# GTM_BallGrippersCircuits.net
KiCad netlist of a schematic drawn in Altium Designer
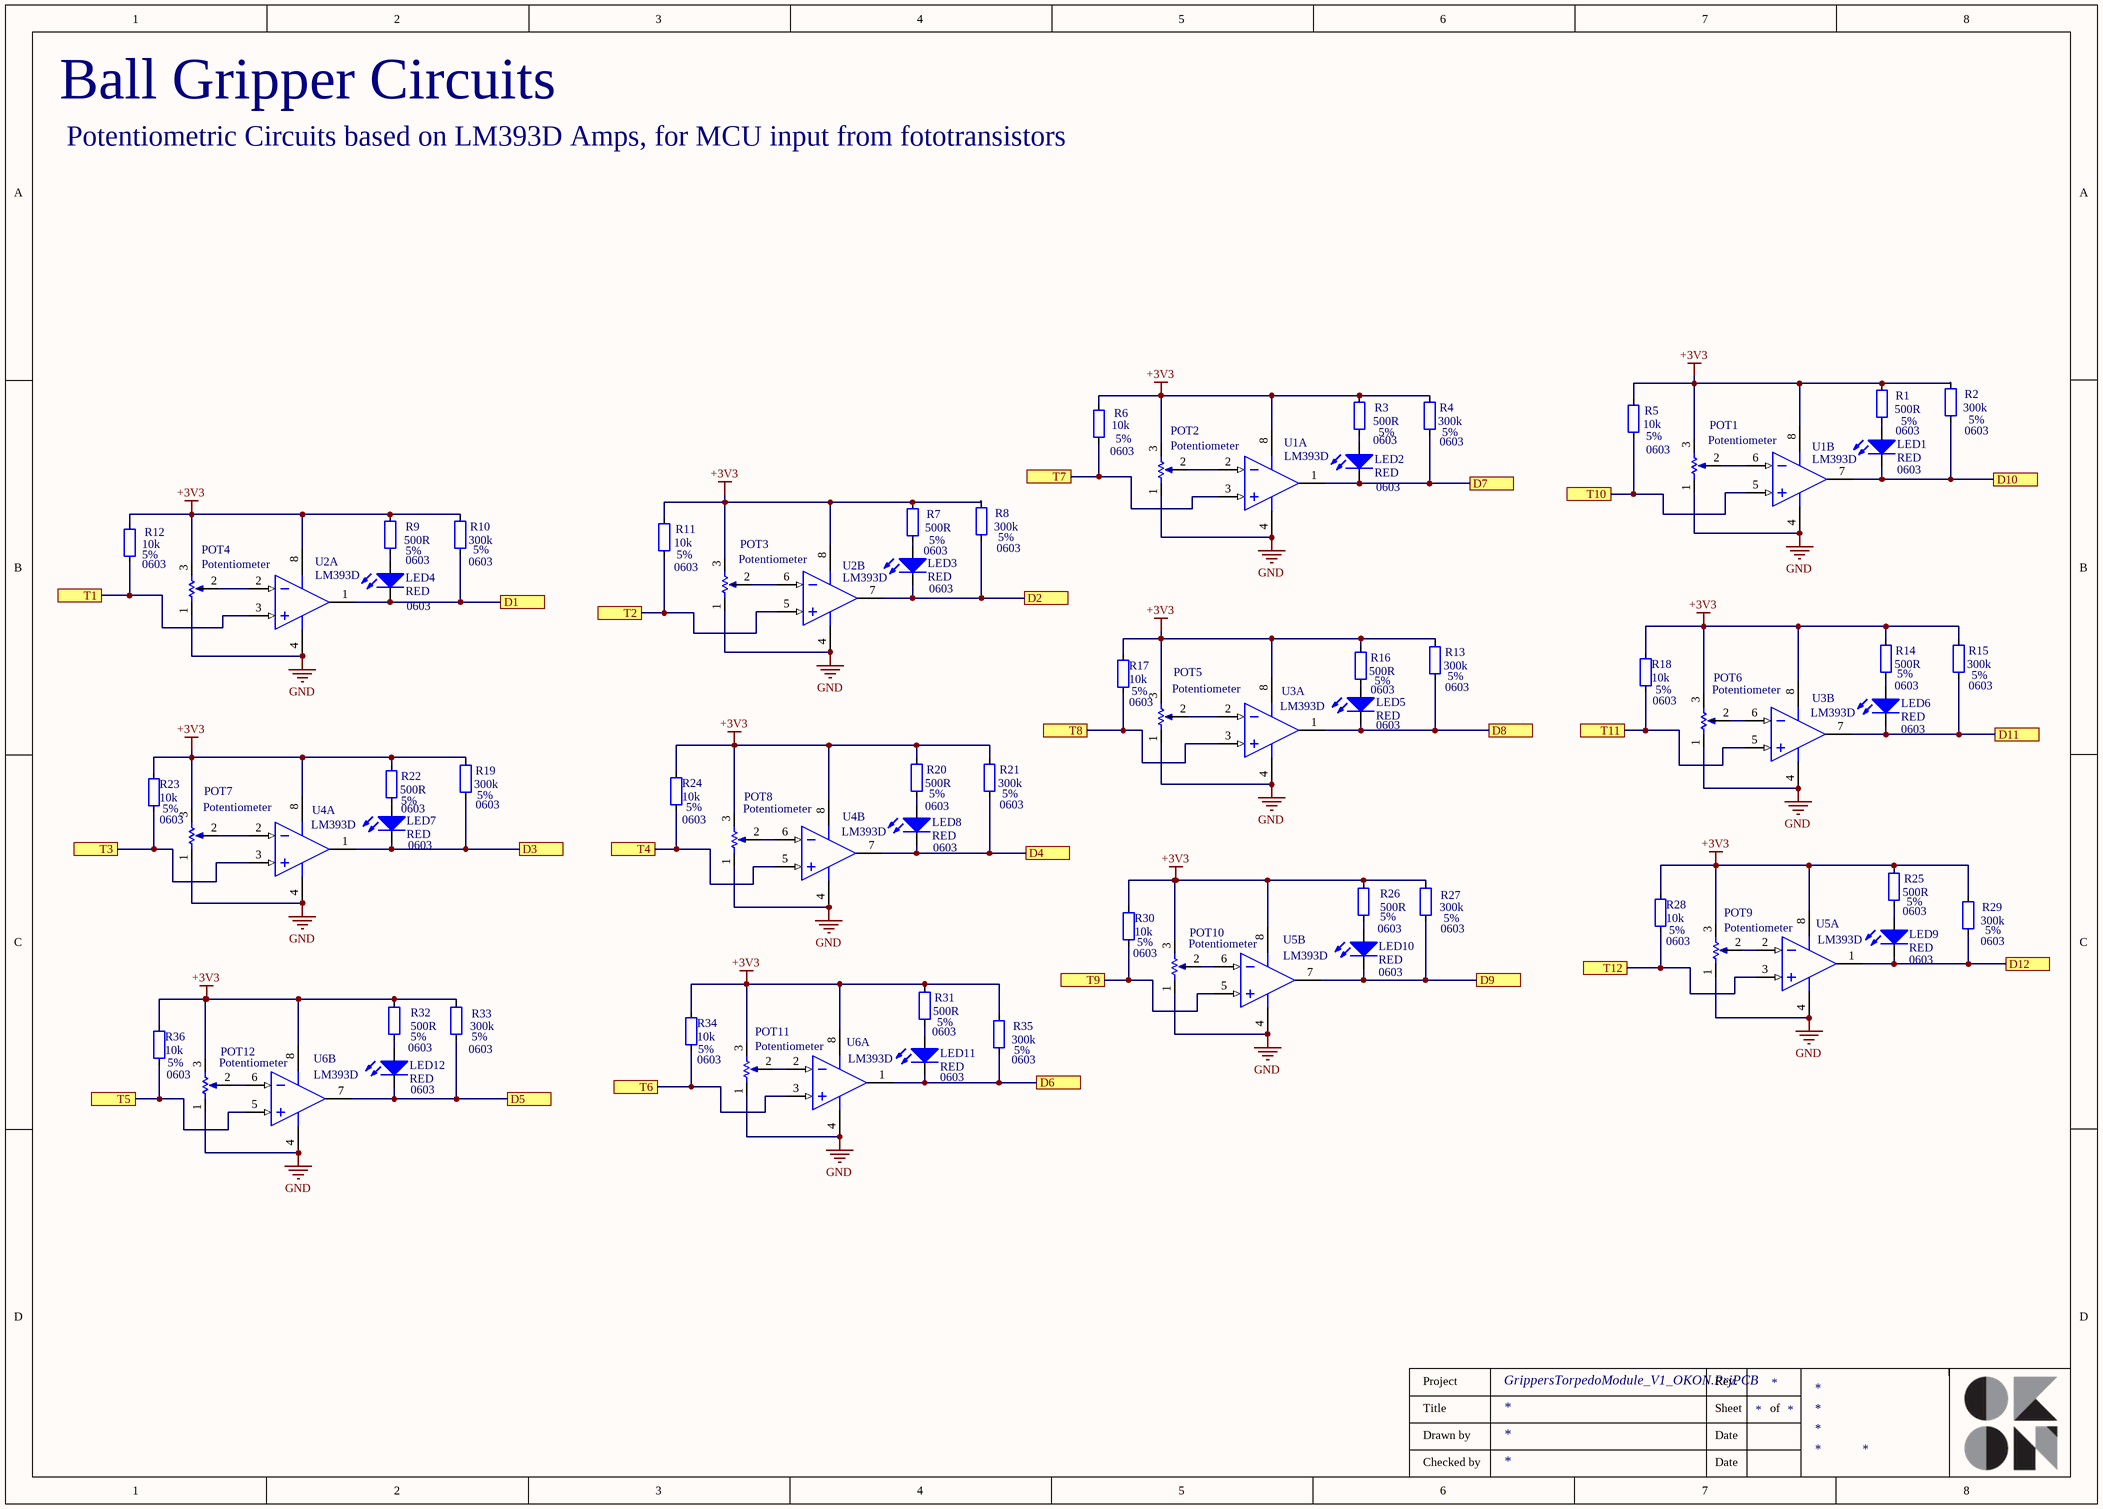
[diagram p0: GTM_BallGrippersCircuits.SchDoc]

(export (version "E")
  (design (tool "Eeschema 10.0.6"))
  (components
    (comp (ref "LED1")
      (value "RED")
      (footprint "0603_led_red")
      (description "Light-emitting diode")
      (fields (field (name "PACKAGE") "0603"))
      (libsource (lib "KNR_Kurs") (part "LED"))
    )
    (comp (ref "LED2")
      (value "RED")
      (footprint "0603_led_red")
      (description "Light-emitting diode")
      (fields (field (name "PACKAGE") "0603"))
      (libsource (lib "KNR_Kurs") (part "LED"))
    )
    (comp (ref "LED3")
      (value "RED")
      (footprint "0603_led_red")
      (description "Light-emitting diode")
      (fields (field (name "PACKAGE") "0603"))
      (libsource (lib "KNR_Kurs") (part "LED"))
    )
    (comp (ref "LED4")
      (value "RED")
      (footprint "0603_led_red")
      (description "Light-emitting diode")
      (fields (field (name "PACKAGE") "0603"))
      (libsource (lib "KNR_Kurs") (part "LED"))
    )
    (comp (ref "LED5")
      (value "RED")
      (footprint "0603_led_red")
      (description "Light-emitting diode")
      (fields (field (name "PACKAGE") "0603"))
      (libsource (lib "KNR_Kurs") (part "LED"))
    )
    (comp (ref "LED6")
      (value "RED")
      (footprint "0603_led_red")
      (description "Light-emitting diode")
      (fields (field (name "PACKAGE") "0603"))
      (libsource (lib "KNR_Kurs") (part "LED"))
    )
    (comp (ref "LED7")
      (value "RED")
      (footprint "0603_led_red")
      (description "Light-emitting diode")
      (fields (field (name "PACKAGE") "0603"))
      (libsource (lib "KNR_Kurs") (part "LED"))
    )
    (comp (ref "LED8")
      (value "RED")
      (footprint "0603_led_red")
      (description "Light-emitting diode")
      (fields (field (name "PACKAGE") "0603"))
      (libsource (lib "KNR_Kurs") (part "LED"))
    )
    (comp (ref "LED9")
      (value "RED")
      (footprint "0603_led_red")
      (description "Light-emitting diode")
      (fields (field (name "PACKAGE") "0603"))
      (libsource (lib "KNR_Kurs") (part "LED"))
    )
    (comp (ref "LED10")
      (value "RED")
      (footprint "0603_led_red")
      (description "Light-emitting diode")
      (fields (field (name "PACKAGE") "0603"))
      (libsource (lib "KNR_Kurs") (part "LED"))
    )
    (comp (ref "LED11")
      (value "RED")
      (footprint "0603_led_red")
      (description "Light-emitting diode")
      (fields (field (name "PACKAGE") "0603"))
      (libsource (lib "KNR_Kurs") (part "LED"))
    )
    (comp (ref "LED12")
      (value "RED")
      (footprint "0603_led_red")
      (description "Light-emitting diode")
      (fields (field (name "PACKAGE") "0603"))
      (libsource (lib "KNR_Kurs") (part "LED"))
    )
    (comp (ref "POT1")
      (value "Potentiometer")
      (footprint "Pot_3296")
      (libsource (lib "Library_Altium_KNR") (part "Potentiometer"))
    )
    (comp (ref "POT2")
      (value "Potentiometer")
      (footprint "Pot_3296")
      (libsource (lib "Library_Altium_KNR") (part "Potentiometer"))
    )
    (comp (ref "POT3")
      (value "Potentiometer")
      (footprint "Pot_3296")
      (libsource (lib "Library_Altium_KNR") (part "Potentiometer"))
    )
    (comp (ref "POT4")
      (value "Potentiometer")
      (footprint "Pot_3296")
      (libsource (lib "Library_Altium_KNR") (part "Potentiometer"))
    )
    (comp (ref "POT5")
      (value "Potentiometer")
      (footprint "Pot_3296")
      (libsource (lib "Library_Altium_KNR") (part "Potentiometer"))
    )
    (comp (ref "POT6")
      (value "Potentiometer")
      (footprint "Pot_3296")
      (libsource (lib "Library_Altium_KNR") (part "Potentiometer"))
    )
    (comp (ref "POT7")
      (value "Potentiometer")
      (footprint "Pot_3296")
      (libsource (lib "Library_Altium_KNR") (part "Potentiometer"))
    )
    (comp (ref "POT8")
      (value "Potentiometer")
      (footprint "Pot_3296")
      (libsource (lib "Library_Altium_KNR") (part "Potentiometer"))
    )
    (comp (ref "POT9")
      (value "Potentiometer")
      (footprint "Pot_3296")
      (libsource (lib "Library_Altium_KNR") (part "Potentiometer"))
    )
    (comp (ref "POT10")
      (value "Potentiometer")
      (footprint "Pot_3296")
      (libsource (lib "Library_Altium_KNR") (part "Potentiometer"))
    )
    (comp (ref "POT11")
      (value "Potentiometer")
      (footprint "Pot_3296")
      (libsource (lib "Library_Altium_KNR") (part "Potentiometer"))
    )
    (comp (ref "POT12")
      (value "Potentiometer")
      (footprint "Pot_3296")
      (libsource (lib "Library_Altium_KNR") (part "Potentiometer"))
    )
    (comp (ref "R1")
      (value "500R")
      (footprint "0603")
      (description "Resistior")
      (fields (field (name "PACKAGE") "0603") (field (name "TOLERANCE") "5%"))
      (libsource (lib "Library_Altium_KNR") (part "RES"))
    )
    (comp (ref "R2")
      (value "300k")
      (footprint "0603")
      (description "Resistior")
      (fields (field (name "PACKAGE") "0603") (field (name "TOLERANCE") "5%"))
      (libsource (lib "Library_Altium_KNR") (part "RES"))
    )
    (comp (ref "R3")
      (value "500R")
      (footprint "0603")
      (description "Resistior")
      (fields (field (name "PACKAGE") "0603") (field (name "TOLERANCE") "5%"))
      (libsource (lib "Library_Altium_KNR") (part "RES"))
    )
    (comp (ref "R4")
      (value "300k")
      (footprint "0603")
      (description "Resistior")
      (fields (field (name "PACKAGE") "0603") (field (name "TOLERANCE") "5%"))
      (libsource (lib "Library_Altium_KNR") (part "RES"))
    )
    (comp (ref "R5")
      (value "10k")
      (footprint "0603")
      (description "Resistior")
      (fields (field (name "PACKAGE") "0603") (field (name "TOLERANCE") "5%"))
      (libsource (lib "Library_Altium_KNR") (part "RES"))
    )
    (comp (ref "R6")
      (value "10k")
      (footprint "0603")
      (description "Resistior")
      (fields (field (name "PACKAGE") "0603") (field (name "TOLERANCE") "5%"))
      (libsource (lib "Library_Altium_KNR") (part "RES"))
    )
    (comp (ref "R7")
      (value "500R")
      (footprint "0603")
      (description "Resistior")
      (fields (field (name "PACKAGE") "0603") (field (name "TOLERANCE") "5%"))
      (libsource (lib "Library_Altium_KNR") (part "RES"))
    )
    (comp (ref "R8")
      (value "300k")
      (footprint "0603")
      (description "Resistior")
      (fields (field (name "PACKAGE") "0603") (field (name "TOLERANCE") "5%"))
      (libsource (lib "Library_Altium_KNR") (part "RES"))
    )
    (comp (ref "R9")
      (value "500R")
      (footprint "0603")
      (description "Resistior")
      (fields (field (name "PACKAGE") "0603") (field (name "TOLERANCE") "5%"))
      (libsource (lib "Library_Altium_KNR") (part "RES"))
    )
    (comp (ref "R10")
      (value "300k")
      (footprint "0603")
      (description "Resistior")
      (fields (field (name "PACKAGE") "0603") (field (name "TOLERANCE") "5%"))
      (libsource (lib "Library_Altium_KNR") (part "RES"))
    )
    (comp (ref "R11")
      (value "10k")
      (footprint "0603")
      (description "Resistior")
      (fields (field (name "PACKAGE") "0603") (field (name "TOLERANCE") "5%"))
      (libsource (lib "Library_Altium_KNR") (part "RES"))
    )
    (comp (ref "R12")
      (value "10k")
      (footprint "0603")
      (description "Resistior")
      (fields (field (name "PACKAGE") "0603") (field (name "TOLERANCE") "5%"))
      (libsource (lib "Library_Altium_KNR") (part "RES"))
    )
    (comp (ref "R13")
      (value "300k")
      (footprint "0603")
      (description "Resistior")
      (fields (field (name "PACKAGE") "0603") (field (name "TOLERANCE") "5%"))
      (libsource (lib "Library_Altium_KNR") (part "RES"))
    )
    (comp (ref "R14")
      (value "500R")
      (footprint "0603")
      (description "Resistior")
      (fields (field (name "PACKAGE") "0603") (field (name "TOLERANCE") "5%"))
      (libsource (lib "Library_Altium_KNR") (part "RES"))
    )
    (comp (ref "R15")
      (value "300k")
      (footprint "0603")
      (description "Resistior")
      (fields (field (name "PACKAGE") "0603") (field (name "TOLERANCE") "5%"))
      (libsource (lib "Library_Altium_KNR") (part "RES"))
    )
    (comp (ref "R16")
      (value "500R")
      (footprint "0603")
      (description "Resistior")
      (fields (field (name "PACKAGE") "0603") (field (name "TOLERANCE") "5%"))
      (libsource (lib "Library_Altium_KNR") (part "RES"))
    )
    (comp (ref "R17")
      (value "10k")
      (footprint "0603")
      (description "Resistior")
      (fields (field (name "PACKAGE") "0603") (field (name "TOLERANCE") "5%"))
      (libsource (lib "Library_Altium_KNR") (part "RES"))
    )
    (comp (ref "R18")
      (value "10k")
      (footprint "0603")
      (description "Resistior")
      (fields (field (name "PACKAGE") "0603") (field (name "TOLERANCE") "5%"))
      (libsource (lib "Library_Altium_KNR") (part "RES"))
    )
    (comp (ref "R19")
      (value "300k")
      (footprint "0603")
      (description "Resistior")
      (fields (field (name "PACKAGE") "0603") (field (name "TOLERANCE") "5%"))
      (libsource (lib "Library_Altium_KNR") (part "RES"))
    )
    (comp (ref "R20")
      (value "500R")
      (footprint "0603")
      (description "Resistior")
      (fields (field (name "PACKAGE") "0603") (field (name "TOLERANCE") "5%"))
      (libsource (lib "Library_Altium_KNR") (part "RES"))
    )
    (comp (ref "R21")
      (value "300k")
      (footprint "0603")
      (description "Resistior")
      (fields (field (name "PACKAGE") "0603") (field (name "TOLERANCE") "5%"))
      (libsource (lib "Library_Altium_KNR") (part "RES"))
    )
    (comp (ref "R22")
      (value "500R")
      (footprint "0603")
      (description "Resistior")
      (fields (field (name "PACKAGE") "0603") (field (name "TOLERANCE") "5%"))
      (libsource (lib "Library_Altium_KNR") (part "RES"))
    )
    (comp (ref "R23")
      (value "10k")
      (footprint "0603")
      (description "Resistior")
      (fields (field (name "PACKAGE") "0603") (field (name "TOLERANCE") "5%"))
      (libsource (lib "Library_Altium_KNR") (part "RES"))
    )
    (comp (ref "R24")
      (value "10k")
      (footprint "0603")
      (description "Resistior")
      (fields (field (name "PACKAGE") "0603") (field (name "TOLERANCE") "5%"))
      (libsource (lib "Library_Altium_KNR") (part "RES"))
    )
    (comp (ref "R25")
      (value "500R")
      (footprint "0603")
      (description "Resistior")
      (fields (field (name "PACKAGE") "0603") (field (name "TOLERANCE") "5%"))
      (libsource (lib "Library_Altium_KNR") (part "RES"))
    )
    (comp (ref "R26")
      (value "500R")
      (footprint "0603")
      (description "Resistior")
      (fields (field (name "PACKAGE") "0603") (field (name "TOLERANCE") "5%"))
      (libsource (lib "Library_Altium_KNR") (part "RES"))
    )
    (comp (ref "R27")
      (value "300k")
      (footprint "0603")
      (description "Resistior")
      (fields (field (name "PACKAGE") "0603") (field (name "TOLERANCE") "5%"))
      (libsource (lib "Library_Altium_KNR") (part "RES"))
    )
    (comp (ref "R28")
      (value "10k")
      (footprint "0603")
      (description "Resistior")
      (fields (field (name "PACKAGE") "0603") (field (name "TOLERANCE") "5%"))
      (libsource (lib "Library_Altium_KNR") (part "RES"))
    )
    (comp (ref "R29")
      (value "300k")
      (footprint "0603")
      (description "Resistior")
      (fields (field (name "PACKAGE") "0603") (field (name "TOLERANCE") "5%"))
      (libsource (lib "Library_Altium_KNR") (part "RES"))
    )
    (comp (ref "R30")
      (value "10k")
      (footprint "0603")
      (description "Resistior")
      (fields (field (name "PACKAGE") "0603") (field (name "TOLERANCE") "5%"))
      (libsource (lib "Library_Altium_KNR") (part "RES"))
    )
    (comp (ref "R31")
      (value "500R")
      (footprint "0603")
      (description "Resistior")
      (fields (field (name "PACKAGE") "0603") (field (name "TOLERANCE") "5%"))
      (libsource (lib "Library_Altium_KNR") (part "RES"))
    )
    (comp (ref "R32")
      (value "500R")
      (footprint "0603")
      (description "Resistior")
      (fields (field (name "PACKAGE") "0603") (field (name "TOLERANCE") "5%"))
      (libsource (lib "Library_Altium_KNR") (part "RES"))
    )
    (comp (ref "R33")
      (value "300k")
      (footprint "0603")
      (description "Resistior")
      (fields (field (name "PACKAGE") "0603") (field (name "TOLERANCE") "5%"))
      (libsource (lib "Library_Altium_KNR") (part "RES"))
    )
    (comp (ref "R34")
      (value "10k")
      (footprint "0603")
      (description "Resistior")
      (fields (field (name "PACKAGE") "0603") (field (name "TOLERANCE") "5%"))
      (libsource (lib "Library_Altium_KNR") (part "RES"))
    )
    (comp (ref "R35")
      (value "300k")
      (footprint "0603")
      (description "Resistior")
      (fields (field (name "PACKAGE") "0603") (field (name "TOLERANCE") "5%"))
      (libsource (lib "Library_Altium_KNR") (part "RES"))
    )
    (comp (ref "R36")
      (value "10k")
      (footprint "0603")
      (description "Resistior")
      (fields (field (name "PACKAGE") "0603") (field (name "TOLERANCE") "5%"))
      (libsource (lib "Library_Altium_KNR") (part "RES"))
    )
    (comp (ref "U1")
      (value "LM393D")
      (footprint "SO8_N")
      (description "Low-Power Dual Voltage Comparator")
      (fields (field (name "PUBLISHER") "Altium Limited"))
      (libsource (lib "ST Analog Comparator") (part "LM393D"))
    )
    (comp (ref "U2")
      (value "LM393D")
      (footprint "SO8_N")
      (description "Low-Power Dual Voltage Comparator")
      (fields (field (name "PUBLISHER") "Altium Limited"))
      (libsource (lib "ST Analog Comparator") (part "LM393D"))
    )
    (comp (ref "U3")
      (value "LM393D")
      (footprint "SO8_N")
      (description "Low-Power Dual Voltage Comparator")
      (fields (field (name "PUBLISHER") "Altium Limited"))
      (libsource (lib "ST Analog Comparator") (part "LM393D"))
    )
    (comp (ref "U4")
      (value "LM393D")
      (footprint "SO8_N")
      (description "Low-Power Dual Voltage Comparator")
      (fields (field (name "PUBLISHER") "Altium Limited"))
      (libsource (lib "ST Analog Comparator") (part "LM393D"))
    )
    (comp (ref "U5")
      (value "LM393D")
      (footprint "SO8_N")
      (description "Low-Power Dual Voltage Comparator")
      (fields (field (name "PUBLISHER") "Altium Limited"))
      (libsource (lib "ST Analog Comparator") (part "LM393D"))
    )
    (comp (ref "U6")
      (value "LM393D")
      (footprint "SO8_N")
      (description "Low-Power Dual Voltage Comparator")
      (fields (field (name "PUBLISHER") "Altium Limited"))
      (libsource (lib "ST Analog Comparator") (part "LM393D"))
    )
  )
  (nets
    (net (code "1") (name "+3V3") (class "Default")
      (node (ref "POT1") (pin "3") (pinfunction "3_3") (pintype "passive"))
      (node (ref "POT10") (pin "3") (pinfunction "3_3") (pintype "passive"))
      (node (ref "POT11") (pin "3") (pinfunction "3_3") (pintype "passive"))
      (node (ref "POT12") (pin "3") (pinfunction "3_3") (pintype "passive"))
      (node (ref "POT2") (pin "3") (pinfunction "3_3") (pintype "passive"))
      (node (ref "POT3") (pin "3") (pinfunction "3_3") (pintype "passive"))
      (node (ref "POT4") (pin "3") (pinfunction "3_3") (pintype "passive"))
      (node (ref "POT5") (pin "3") (pinfunction "3_3") (pintype "passive"))
      (node (ref "POT6") (pin "3") (pinfunction "3_3") (pintype "passive"))
      (node (ref "POT7") (pin "3") (pinfunction "3_3") (pintype "passive"))
      (node (ref "POT8") (pin "3") (pinfunction "3_3") (pintype "passive"))
      (node (ref "POT9") (pin "3") (pinfunction "3_3") (pintype "passive"))
      (node (ref "R1") (pin "2") (pinfunction "2_2") (pintype "passive"))
      (node (ref "R10") (pin "2") (pinfunction "2_2") (pintype "passive"))
      (node (ref "R11") (pin "2") (pinfunction "2_2") (pintype "passive"))
      (node (ref "R12") (pin "2") (pinfunction "2_2") (pintype "passive"))
      (node (ref "R13") (pin "2") (pinfunction "2_2") (pintype "passive"))
      (node (ref "R14") (pin "2") (pinfunction "2_2") (pintype "passive"))
      (node (ref "R15") (pin "2") (pinfunction "2_2") (pintype "passive"))
      (node (ref "R16") (pin "2") (pinfunction "2_2") (pintype "passive"))
      (node (ref "R17") (pin "2") (pinfunction "2_2") (pintype "passive"))
      (node (ref "R18") (pin "2") (pinfunction "2_2") (pintype "passive"))
      (node (ref "R19") (pin "2") (pinfunction "2_2") (pintype "passive"))
      (node (ref "R2") (pin "2") (pinfunction "2_2") (pintype "passive"))
      (node (ref "R20") (pin "2") (pinfunction "2_2") (pintype "passive"))
      (node (ref "R21") (pin "2") (pinfunction "2_2") (pintype "passive"))
      (node (ref "R22") (pin "2") (pinfunction "2_2") (pintype "passive"))
      (node (ref "R23") (pin "2") (pinfunction "2_2") (pintype "passive"))
      (node (ref "R24") (pin "2") (pinfunction "2_2") (pintype "passive"))
      (node (ref "R25") (pin "2") (pinfunction "2_2") (pintype "passive"))
      (node (ref "R26") (pin "2") (pinfunction "2_2") (pintype "passive"))
      (node (ref "R27") (pin "2") (pinfunction "2_2") (pintype "passive"))
      (node (ref "R28") (pin "2") (pinfunction "2_2") (pintype "passive"))
      (node (ref "R29") (pin "2") (pinfunction "2_2") (pintype "passive"))
      (node (ref "R3") (pin "2") (pinfunction "2_2") (pintype "passive"))
      (node (ref "R30") (pin "2") (pinfunction "2_2") (pintype "passive"))
      (node (ref "R31") (pin "2") (pinfunction "2_2") (pintype "passive"))
      (node (ref "R32") (pin "2") (pinfunction "2_2") (pintype "passive"))
      (node (ref "R33") (pin "2") (pinfunction "2_2") (pintype "passive"))
      (node (ref "R34") (pin "2") (pinfunction "2_2") (pintype "passive"))
      (node (ref "R35") (pin "2") (pinfunction "2_2") (pintype "passive"))
      (node (ref "R36") (pin "2") (pinfunction "2_2") (pintype "passive"))
      (node (ref "R4") (pin "2") (pinfunction "2_2") (pintype "passive"))
      (node (ref "R5") (pin "2") (pinfunction "2_2") (pintype "passive"))
      (node (ref "R6") (pin "2") (pinfunction "2_2") (pintype "passive"))
      (node (ref "R7") (pin "2") (pinfunction "2_2") (pintype "passive"))
      (node (ref "R8") (pin "2") (pinfunction "2_2") (pintype "passive"))
      (node (ref "R9") (pin "2") (pinfunction "2_2") (pintype "passive"))
      (node (ref "U1") (pin "8") (pinfunction "V+_8") (pintype "power_in"))
      (node (ref "U2") (pin "8") (pinfunction "V+_8") (pintype "power_in"))
      (node (ref "U3") (pin "8") (pinfunction "V+_8") (pintype "power_in"))
      (node (ref "U4") (pin "8") (pinfunction "V+_8") (pintype "power_in"))
      (node (ref "U5") (pin "8") (pinfunction "V+_8") (pintype "power_in"))
      (node (ref "U6") (pin "8") (pinfunction "V+_8") (pintype "power_in"))
    )
    (net (code "2") (name "/D1") (class "Default")
      (node (ref "LED4") (pin "2") (pinfunction "K_2") (pintype "passive"))
      (node (ref "R10") (pin "1") (pinfunction "1_1") (pintype "passive"))
      (node (ref "U2") (pin "1") (pinfunction "OUT_1") (pintype "open_collector"))
    )
    (net (code "3") (name "/D2") (class "Default")
      (node (ref "LED3") (pin "2") (pinfunction "K_2") (pintype "passive"))
      (node (ref "R8") (pin "1") (pinfunction "1_1") (pintype "passive"))
      (node (ref "U2") (pin "7") (pinfunction "OUT_7") (pintype "open_collector"))
    )
    (net (code "4") (name "/D3") (class "Default")
      (node (ref "LED7") (pin "2") (pinfunction "K_2") (pintype "passive"))
      (node (ref "R19") (pin "1") (pinfunction "1_1") (pintype "passive"))
      (node (ref "U4") (pin "1") (pinfunction "OUT_1") (pintype "open_collector"))
    )
    (net (code "5") (name "/D4") (class "Default")
      (node (ref "LED8") (pin "2") (pinfunction "K_2") (pintype "passive"))
      (node (ref "R21") (pin "1") (pinfunction "1_1") (pintype "passive"))
      (node (ref "U4") (pin "7") (pinfunction "OUT_7") (pintype "open_collector"))
    )
    (net (code "6") (name "/D5") (class "Default")
      (node (ref "LED12") (pin "2") (pinfunction "K_2") (pintype "passive"))
      (node (ref "R33") (pin "1") (pinfunction "1_1") (pintype "passive"))
      (node (ref "U6") (pin "7") (pinfunction "OUT_7") (pintype "open_collector"))
    )
    (net (code "7") (name "/D6") (class "Default")
      (node (ref "LED11") (pin "2") (pinfunction "K_2") (pintype "passive"))
      (node (ref "R35") (pin "1") (pinfunction "1_1") (pintype "passive"))
      (node (ref "U6") (pin "1") (pinfunction "OUT_1") (pintype "open_collector"))
    )
    (net (code "8") (name "/D7") (class "Default")
      (node (ref "LED2") (pin "2") (pinfunction "K_2") (pintype "passive"))
      (node (ref "R4") (pin "1") (pinfunction "1_1") (pintype "passive"))
      (node (ref "U1") (pin "1") (pinfunction "OUT_1") (pintype "open_collector"))
    )
    (net (code "9") (name "/D8") (class "Default")
      (node (ref "LED5") (pin "2") (pinfunction "K_2") (pintype "passive"))
      (node (ref "R13") (pin "1") (pinfunction "1_1") (pintype "passive"))
      (node (ref "U3") (pin "1") (pinfunction "OUT_1") (pintype "open_collector"))
    )
    (net (code "10") (name "/D9") (class "Default")
      (node (ref "LED10") (pin "2") (pinfunction "K_2") (pintype "passive"))
      (node (ref "R27") (pin "1") (pinfunction "1_1") (pintype "passive"))
      (node (ref "U5") (pin "7") (pinfunction "OUT_7") (pintype "open_collector"))
    )
    (net (code "11") (name "/D10") (class "Default")
      (node (ref "LED1") (pin "2") (pinfunction "K_2") (pintype "passive"))
      (node (ref "R2") (pin "1") (pinfunction "1_1") (pintype "passive"))
      (node (ref "U1") (pin "7") (pinfunction "OUT_7") (pintype "open_collector"))
    )
    (net (code "12") (name "/D11") (class "Default")
      (node (ref "LED6") (pin "2") (pinfunction "K_2") (pintype "passive"))
      (node (ref "R15") (pin "1") (pinfunction "1_1") (pintype "passive"))
      (node (ref "U3") (pin "7") (pinfunction "OUT_7") (pintype "open_collector"))
    )
    (net (code "13") (name "/D12") (class "Default")
      (node (ref "LED9") (pin "2") (pinfunction "K_2") (pintype "passive"))
      (node (ref "R29") (pin "1") (pinfunction "1_1") (pintype "passive"))
      (node (ref "U5") (pin "1") (pinfunction "OUT_1") (pintype "open_collector"))
    )
    (net (code "14") (name "/T1") (class "Default")
      (node (ref "R12") (pin "1") (pinfunction "1_1") (pintype "passive"))
      (node (ref "U2") (pin "3") (pinfunction "IN+_3") (pintype "input"))
    )
    (net (code "15") (name "/T2") (class "Default")
      (node (ref "R11") (pin "1") (pinfunction "1_1") (pintype "passive"))
      (node (ref "U2") (pin "5") (pinfunction "IN+_5") (pintype "input"))
    )
    (net (code "16") (name "/T3") (class "Default")
      (node (ref "R23") (pin "1") (pinfunction "1_1") (pintype "passive"))
      (node (ref "U4") (pin "3") (pinfunction "IN+_3") (pintype "input"))
    )
    (net (code "17") (name "/T4") (class "Default")
      (node (ref "R24") (pin "1") (pinfunction "1_1") (pintype "passive"))
      (node (ref "U4") (pin "5") (pinfunction "IN+_5") (pintype "input"))
    )
    (net (code "18") (name "/T5") (class "Default")
      (node (ref "R36") (pin "1") (pinfunction "1_1") (pintype "passive"))
      (node (ref "U6") (pin "5") (pinfunction "IN+_5") (pintype "input"))
    )
    (net (code "19") (name "/T6") (class "Default")
      (node (ref "R34") (pin "1") (pinfunction "1_1") (pintype "passive"))
      (node (ref "U6") (pin "3") (pinfunction "IN+_3") (pintype "input"))
    )
    (net (code "20") (name "/T7") (class "Default")
      (node (ref "R6") (pin "1") (pinfunction "1_1") (pintype "passive"))
      (node (ref "U1") (pin "3") (pinfunction "IN+_3") (pintype "input"))
    )
    (net (code "21") (name "/T8") (class "Default")
      (node (ref "R17") (pin "1") (pinfunction "1_1") (pintype "passive"))
      (node (ref "U3") (pin "3") (pinfunction "IN+_3") (pintype "input"))
    )
    (net (code "22") (name "/T9") (class "Default")
      (node (ref "R30") (pin "1") (pinfunction "1_1") (pintype "passive"))
      (node (ref "U5") (pin "5") (pinfunction "IN+_5") (pintype "input"))
    )
    (net (code "23") (name "/T10") (class "Default")
      (node (ref "R5") (pin "1") (pinfunction "1_1") (pintype "passive"))
      (node (ref "U1") (pin "5") (pinfunction "IN+_5") (pintype "input"))
    )
    (net (code "24") (name "/T11") (class "Default")
      (node (ref "R18") (pin "1") (pinfunction "1_1") (pintype "passive"))
      (node (ref "U3") (pin "5") (pinfunction "IN+_5") (pintype "input"))
    )
    (net (code "25") (name "/T12") (class "Default")
      (node (ref "R28") (pin "1") (pinfunction "1_1") (pintype "passive"))
      (node (ref "U5") (pin "3") (pinfunction "IN+_3") (pintype "input"))
    )
    (net (code "26") (name "GND") (class "Default")
      (node (ref "POT1") (pin "1") (pinfunction "1_1") (pintype "passive"))
      (node (ref "POT10") (pin "1") (pinfunction "1_1") (pintype "passive"))
      (node (ref "POT11") (pin "1") (pinfunction "1_1") (pintype "passive"))
      (node (ref "POT12") (pin "1") (pinfunction "1_1") (pintype "passive"))
      (node (ref "POT2") (pin "1") (pinfunction "1_1") (pintype "passive"))
      (node (ref "POT3") (pin "1") (pinfunction "1_1") (pintype "passive"))
      (node (ref "POT4") (pin "1") (pinfunction "1_1") (pintype "passive"))
      (node (ref "POT5") (pin "1") (pinfunction "1_1") (pintype "passive"))
      (node (ref "POT6") (pin "1") (pinfunction "1_1") (pintype "passive"))
      (node (ref "POT7") (pin "1") (pinfunction "1_1") (pintype "passive"))
      (node (ref "POT8") (pin "1") (pinfunction "1_1") (pintype "passive"))
      (node (ref "POT9") (pin "1") (pinfunction "1_1") (pintype "passive"))
      (node (ref "U1") (pin "4") (pinfunction "V-_4") (pintype "power_in"))
      (node (ref "U2") (pin "4") (pinfunction "V-_4") (pintype "power_in"))
      (node (ref "U3") (pin "4") (pinfunction "V-_4") (pintype "power_in"))
      (node (ref "U4") (pin "4") (pinfunction "V-_4") (pintype "power_in"))
      (node (ref "U5") (pin "4") (pinfunction "V-_4") (pintype "power_in"))
      (node (ref "U6") (pin "4") (pinfunction "V-_4") (pintype "power_in"))
    )
    (net (code "27") (name "Net-(LED1-A)") (class "Default")
      (node (ref "LED1") (pin "1") (pinfunction "A_1") (pintype "passive"))
      (node (ref "R1") (pin "1") (pinfunction "1_1") (pintype "passive"))
    )
    (net (code "28") (name "Net-(LED2-A)") (class "Default")
      (node (ref "LED2") (pin "1") (pinfunction "A_1") (pintype "passive"))
      (node (ref "R3") (pin "1") (pinfunction "1_1") (pintype "passive"))
    )
    (net (code "29") (name "Net-(LED3-A)") (class "Default")
      (node (ref "LED3") (pin "1") (pinfunction "A_1") (pintype "passive"))
      (node (ref "R7") (pin "1") (pinfunction "1_1") (pintype "passive"))
    )
    (net (code "30") (name "Net-(LED4-A)") (class "Default")
      (node (ref "LED4") (pin "1") (pinfunction "A_1") (pintype "passive"))
      (node (ref "R9") (pin "1") (pinfunction "1_1") (pintype "passive"))
    )
    (net (code "31") (name "Net-(LED5-A)") (class "Default")
      (node (ref "LED5") (pin "1") (pinfunction "A_1") (pintype "passive"))
      (node (ref "R16") (pin "1") (pinfunction "1_1") (pintype "passive"))
    )
    (net (code "32") (name "Net-(LED6-A)") (class "Default")
      (node (ref "LED6") (pin "1") (pinfunction "A_1") (pintype "passive"))
      (node (ref "R14") (pin "1") (pinfunction "1_1") (pintype "passive"))
    )
    (net (code "33") (name "Net-(LED7-A)") (class "Default")
      (node (ref "LED7") (pin "1") (pinfunction "A_1") (pintype "passive"))
      (node (ref "R22") (pin "1") (pinfunction "1_1") (pintype "passive"))
    )
    (net (code "34") (name "Net-(LED8-A)") (class "Default")
      (node (ref "LED8") (pin "1") (pinfunction "A_1") (pintype "passive"))
      (node (ref "R20") (pin "1") (pinfunction "1_1") (pintype "passive"))
    )
    (net (code "35") (name "Net-(LED9-A)") (class "Default")
      (node (ref "LED9") (pin "1") (pinfunction "A_1") (pintype "passive"))
      (node (ref "R25") (pin "1") (pinfunction "1_1") (pintype "passive"))
    )
    (net (code "36") (name "Net-(LED10-A)") (class "Default")
      (node (ref "LED10") (pin "1") (pinfunction "A_1") (pintype "passive"))
      (node (ref "R26") (pin "1") (pinfunction "1_1") (pintype "passive"))
    )
    (net (code "37") (name "Net-(LED11-A)") (class "Default")
      (node (ref "LED11") (pin "1") (pinfunction "A_1") (pintype "passive"))
      (node (ref "R31") (pin "1") (pinfunction "1_1") (pintype "passive"))
    )
    (net (code "38") (name "Net-(LED12-A)") (class "Default")
      (node (ref "LED12") (pin "1") (pinfunction "A_1") (pintype "passive"))
      (node (ref "R32") (pin "1") (pinfunction "1_1") (pintype "passive"))
    )
    (net (code "39") (name "Net-(U1A-IN-)") (class "Default")
      (node (ref "POT2") (pin "2") (pinfunction "2_2") (pintype "passive"))
      (node (ref "U1") (pin "2") (pinfunction "IN-_2") (pintype "input"))
    )
    (net (code "40") (name "Net-(U1B-IN-)") (class "Default")
      (node (ref "POT1") (pin "2") (pinfunction "2_2") (pintype "passive"))
      (node (ref "U1") (pin "6") (pinfunction "IN-_6") (pintype "input"))
    )
    (net (code "41") (name "Net-(U2A-IN-)") (class "Default")
      (node (ref "POT4") (pin "2") (pinfunction "2_2") (pintype "passive"))
      (node (ref "U2") (pin "2") (pinfunction "IN-_2") (pintype "input"))
    )
    (net (code "42") (name "Net-(U2B-IN-)") (class "Default")
      (node (ref "POT3") (pin "2") (pinfunction "2_2") (pintype "passive"))
      (node (ref "U2") (pin "6") (pinfunction "IN-_6") (pintype "input"))
    )
    (net (code "43") (name "Net-(U3A-IN-)") (class "Default")
      (node (ref "POT5") (pin "2") (pinfunction "2_2") (pintype "passive"))
      (node (ref "U3") (pin "2") (pinfunction "IN-_2") (pintype "input"))
    )
    (net (code "44") (name "Net-(U3B-IN-)") (class "Default")
      (node (ref "POT6") (pin "2") (pinfunction "2_2") (pintype "passive"))
      (node (ref "U3") (pin "6") (pinfunction "IN-_6") (pintype "input"))
    )
    (net (code "45") (name "Net-(U4A-IN-)") (class "Default")
      (node (ref "POT7") (pin "2") (pinfunction "2_2") (pintype "passive"))
      (node (ref "U4") (pin "2") (pinfunction "IN-_2") (pintype "input"))
    )
    (net (code "46") (name "Net-(U4B-IN-)") (class "Default")
      (node (ref "POT8") (pin "2") (pinfunction "2_2") (pintype "passive"))
      (node (ref "U4") (pin "6") (pinfunction "IN-_6") (pintype "input"))
    )
    (net (code "47") (name "Net-(U5A-IN-)") (class "Default")
      (node (ref "POT9") (pin "2") (pinfunction "2_2") (pintype "passive"))
      (node (ref "U5") (pin "2") (pinfunction "IN-_2") (pintype "input"))
    )
    (net (code "48") (name "Net-(U5B-IN-)") (class "Default")
      (node (ref "POT10") (pin "2") (pinfunction "2_2") (pintype "passive"))
      (node (ref "U5") (pin "6") (pinfunction "IN-_6") (pintype "input"))
    )
    (net (code "49") (name "Net-(U6A-IN-)") (class "Default")
      (node (ref "POT11") (pin "2") (pinfunction "2_2") (pintype "passive"))
      (node (ref "U6") (pin "2") (pinfunction "IN-_2") (pintype "input"))
    )
    (net (code "50") (name "Net-(U6B-IN-)") (class "Default")
      (node (ref "POT12") (pin "2") (pinfunction "2_2") (pintype "passive"))
      (node (ref "U6") (pin "6") (pinfunction "IN-_6") (pintype "input"))
    )
  )
)
